# GPIO.net
KiCad netlist of a schematic drawn in Altium Designer
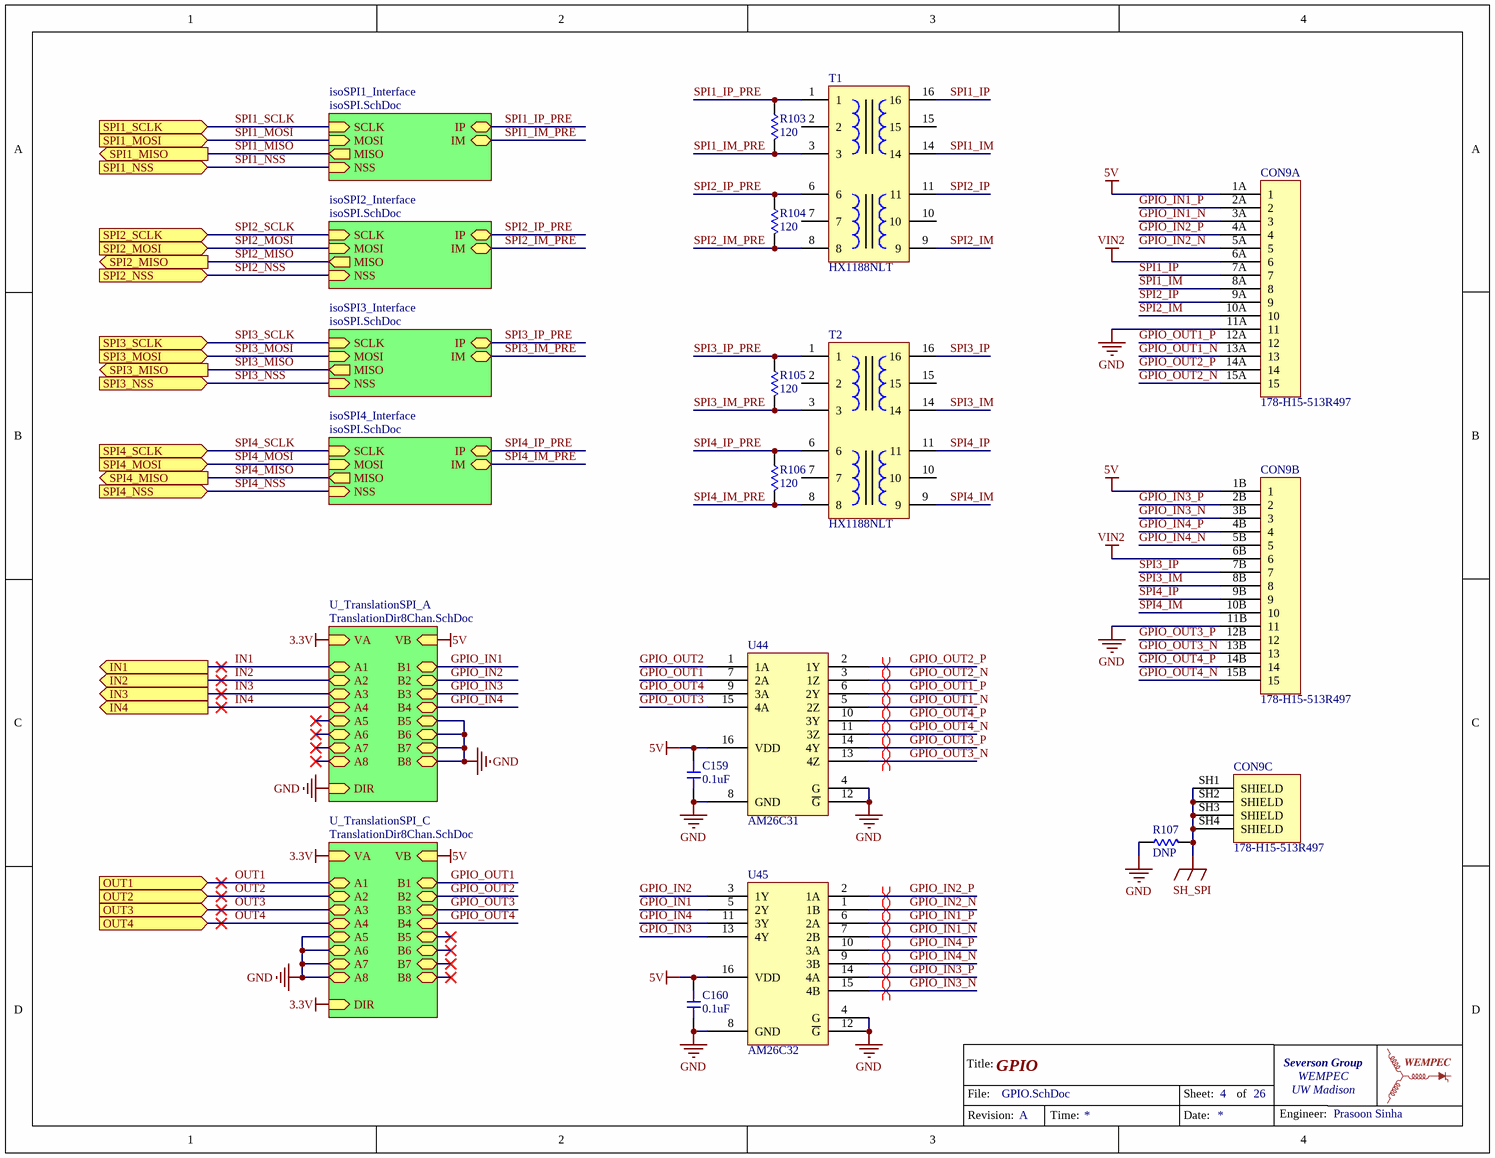
[diagram p0: GPIO.SchDoc]

(export (version "E")
  (design (tool "Eeschema 10.0.6"))
  (components
    (comp (ref "C159")
      (value "0.1uF")
      (footprint "AMDC:0603-CAP")
      (description "Capacitor")
      (libsource (lib "AMDC") (part "Capacitor"))
    )
    (comp (ref "C160")
      (value "0.1uF")
      (footprint "AMDC:0603-CAP")
      (description "Capacitor")
      (libsource (lib "AMDC") (part "Capacitor"))
    )
    (comp (ref "CON9")
      (value "178-H15-513R497")
      (footprint "AMDC:178-H15-513R497")
      (description "CONN D-SUB RCPT/RCPT 15/15POS RA")
      (libsource (lib "AMDC") (part "178-H15-513R497"))
    )
    (comp (ref "R103")
      (value "120")
      (footprint "AMDC:0603-RES")
      (description "Resistor")
      (libsource (lib "AMDC") (part "Resistor"))
    )
    (comp (ref "R104")
      (value "120")
      (footprint "AMDC:0603-RES")
      (description "Resistor")
      (libsource (lib "AMDC") (part "Resistor"))
    )
    (comp (ref "R105")
      (value "120")
      (footprint "AMDC:0603-RES")
      (description "Resistor")
      (libsource (lib "AMDC") (part "Resistor"))
    )
    (comp (ref "R106")
      (value "120")
      (footprint "AMDC:0603-RES")
      (description "Resistor")
      (libsource (lib "AMDC") (part "Resistor"))
    )
    (comp (ref "R107")
      (value "DNP")
      (footprint "AMDC:0603-RES")
      (description "Resistor")
      (libsource (lib "AMDC") (part "Resistor"))
    )
    (comp (ref "T1")
      (value "HX1188NLT")
      (footprint "AMDC:HX1188NLT")
      (description "XFRMR MAGNETIC 1PORT 1:1 10/100")
      (libsource (lib "AMDC") (part "HX1188NLT"))
    )
    (comp (ref "T2")
      (value "HX1188NLT")
      (footprint "AMDC:HX1188NLT")
      (description "XFRMR MAGNETIC 1PORT 1:1 10/100")
      (libsource (lib "AMDC") (part "HX1188NLT"))
    )
    (comp (ref "U44")
      (value "AM26C31")
      (footprint "AMDC:TSOP65P640X120-16N")
      (description "IC DRIVER 4/0 16TSSOP")
      (libsource (lib "AMDC") (part "AM26C31"))
    )
    (comp (ref "U45")
      (value "AM26C32")
      (footprint "AMDC:TSOP65P640X120-16N")
      (description "IC RCVR RS422 QUAD DIFF 16TSSOP")
      (libsource (lib "AMDC") (part "AM26C32"))
    )
  )
  (nets
    (net (code "9") (name "/GPIO_IN1") (class "Default")
      (node (ref "U45") (pin "5") (pinfunction "2Y_5") (pintype "passive"))
    )
    (net (code "10") (name "/GPIO_IN1_N") (class "Default")
      (node (ref "CON9") (pin "3A") (pinfunction "3_3A") (pintype "passive"))
      (node (ref "U45") (pin "7") (pinfunction "2B_7") (pintype "passive"))
    )
    (net (code "11") (name "/GPIO_IN1_P") (class "Default")
      (node (ref "CON9") (pin "2A") (pinfunction "2_2A") (pintype "passive"))
      (node (ref "U45") (pin "6") (pinfunction "2A_6") (pintype "passive"))
    )
    (net (code "12") (name "/GPIO_IN2") (class "Default")
      (node (ref "U45") (pin "3") (pinfunction "1Y_3") (pintype "passive"))
    )
    (net (code "13") (name "/GPIO_IN2_N") (class "Default")
      (node (ref "CON9") (pin "5A") (pinfunction "5_5A") (pintype "passive"))
      (node (ref "U45") (pin "1") (pinfunction "1B_1") (pintype "passive"))
    )
    (net (code "14") (name "/GPIO_IN2_P") (class "Default")
      (node (ref "CON9") (pin "4A") (pinfunction "4_4A") (pintype "passive"))
      (node (ref "U45") (pin "2") (pinfunction "1A_2") (pintype "passive"))
    )
    (net (code "15") (name "/GPIO_IN3") (class "Default")
      (node (ref "U45") (pin "13") (pinfunction "4Y_13") (pintype "passive"))
    )
    (net (code "16") (name "/GPIO_IN3_N") (class "Default")
      (node (ref "CON9") (pin "3B") (pinfunction "3_3B") (pintype "passive"))
      (node (ref "U45") (pin "15") (pinfunction "4B_15") (pintype "passive"))
    )
    (net (code "17") (name "/GPIO_IN3_P") (class "Default")
      (node (ref "CON9") (pin "2B") (pinfunction "2_2B") (pintype "passive"))
      (node (ref "U45") (pin "14") (pinfunction "4A_14") (pintype "passive"))
    )
    (net (code "18") (name "/GPIO_IN4") (class "Default")
      (node (ref "U45") (pin "11") (pinfunction "3Y_11") (pintype "passive"))
    )
    (net (code "19") (name "/GPIO_IN4_N") (class "Default")
      (node (ref "CON9") (pin "5B") (pinfunction "5_5B") (pintype "passive"))
      (node (ref "U45") (pin "9") (pinfunction "3B_9") (pintype "passive"))
    )
    (net (code "20") (name "/GPIO_IN4_P") (class "Default")
      (node (ref "CON9") (pin "4B") (pinfunction "4_4B") (pintype "passive"))
      (node (ref "U45") (pin "10") (pinfunction "3A_10") (pintype "passive"))
    )
    (net (code "21") (name "/GPIO_OUT1") (class "Default")
      (node (ref "U44") (pin "7") (pinfunction "2A_7") (pintype "passive"))
    )
    (net (code "22") (name "/GPIO_OUT1_N") (class "Default")
      (node (ref "CON9") (pin "13A") (pinfunction "13_13A") (pintype "passive"))
      (node (ref "U44") (pin "5") (pinfunction "2Z_5") (pintype "passive"))
    )
    (net (code "23") (name "/GPIO_OUT1_P") (class "Default")
      (node (ref "CON9") (pin "12A") (pinfunction "12_12A") (pintype "passive"))
      (node (ref "U44") (pin "6") (pinfunction "2Y_6") (pintype "passive"))
    )
    (net (code "24") (name "/GPIO_OUT2") (class "Default")
      (node (ref "U44") (pin "1") (pinfunction "1A_1") (pintype "passive"))
    )
    (net (code "25") (name "/GPIO_OUT2_N") (class "Default")
      (node (ref "CON9") (pin "15A") (pinfunction "15_15A") (pintype "passive"))
      (node (ref "U44") (pin "3") (pinfunction "1Z_3") (pintype "passive"))
    )
    (net (code "26") (name "/GPIO_OUT2_P") (class "Default")
      (node (ref "CON9") (pin "14A") (pinfunction "14_14A") (pintype "passive"))
      (node (ref "U44") (pin "2") (pinfunction "1Y_2") (pintype "passive"))
    )
    (net (code "27") (name "/GPIO_OUT3") (class "Default")
      (node (ref "U44") (pin "15") (pinfunction "4A_15") (pintype "passive"))
    )
    (net (code "28") (name "/GPIO_OUT3_N") (class "Default")
      (node (ref "CON9") (pin "13B") (pinfunction "13_13B") (pintype "passive"))
      (node (ref "U44") (pin "13") (pinfunction "4Z_13") (pintype "passive"))
    )
    (net (code "29") (name "/GPIO_OUT3_P") (class "Default")
      (node (ref "CON9") (pin "12B") (pinfunction "12_12B") (pintype "passive"))
      (node (ref "U44") (pin "14") (pinfunction "4Y_14") (pintype "passive"))
    )
    (net (code "30") (name "/GPIO_OUT4") (class "Default")
      (node (ref "U44") (pin "9") (pinfunction "3A_9") (pintype "passive"))
    )
    (net (code "31") (name "/GPIO_OUT4_N") (class "Default")
      (node (ref "CON9") (pin "15B") (pinfunction "15_15B") (pintype "passive"))
      (node (ref "U44") (pin "11") (pinfunction "3Z_11") (pintype "passive"))
    )
    (net (code "32") (name "/GPIO_OUT4_P") (class "Default")
      (node (ref "CON9") (pin "14B") (pinfunction "14_14B") (pintype "passive"))
      (node (ref "U44") (pin "10") (pinfunction "3Y_10") (pintype "passive"))
    )
    (net (code "41") (name "/SPI1_IM") (class "Default")
      (node (ref "CON9") (pin "8A") (pinfunction "8_8A") (pintype "passive"))
      (node (ref "T1") (pin "14") (pinfunction "14_14") (pintype "passive"))
    )
    (net (code "42") (name "/SPI1_IM_PRE") (class "Default")
      (node (ref "R103") (pin "2") (pinfunction "2_2") (pintype "passive"))
      (node (ref "T1") (pin "3") (pinfunction "3_3") (pintype "passive"))
    )
    (net (code "43") (name "/SPI1_IP") (class "Default")
      (node (ref "CON9") (pin "7A") (pinfunction "7_7A") (pintype "passive"))
      (node (ref "T1") (pin "16") (pinfunction "16_16") (pintype "passive"))
    )
    (net (code "44") (name "/SPI1_IP_PRE") (class "Default")
      (node (ref "R103") (pin "1") (pinfunction "1_1") (pintype "passive"))
      (node (ref "T1") (pin "1") (pinfunction "1_1") (pintype "passive"))
    )
    (net (code "49") (name "/SPI2_IM") (class "Default")
      (node (ref "CON9") (pin "10A") (pinfunction "10_10A") (pintype "passive"))
      (node (ref "T1") (pin "9") (pinfunction "9_9") (pintype "passive"))
    )
    (net (code "50") (name "/SPI2_IM_PRE") (class "Default")
      (node (ref "R104") (pin "2") (pinfunction "2_2") (pintype "passive"))
      (node (ref "T1") (pin "8") (pinfunction "8_8") (pintype "passive"))
    )
    (net (code "51") (name "/SPI2_IP") (class "Default")
      (node (ref "CON9") (pin "9A") (pinfunction "9_9A") (pintype "passive"))
      (node (ref "T1") (pin "11") (pinfunction "11_11") (pintype "passive"))
    )
    (net (code "52") (name "/SPI2_IP_PRE") (class "Default")
      (node (ref "R104") (pin "1") (pinfunction "1_1") (pintype "passive"))
      (node (ref "T1") (pin "6") (pinfunction "6_6") (pintype "passive"))
    )
    (net (code "57") (name "/SPI3_IM") (class "Default")
      (node (ref "CON9") (pin "8B") (pinfunction "8_8B") (pintype "passive"))
      (node (ref "T2") (pin "14") (pinfunction "14_14") (pintype "passive"))
    )
    (net (code "58") (name "/SPI3_IM_PRE") (class "Default")
      (node (ref "R105") (pin "2") (pinfunction "2_2") (pintype "passive"))
      (node (ref "T2") (pin "3") (pinfunction "3_3") (pintype "passive"))
    )
    (net (code "59") (name "/SPI3_IP") (class "Default")
      (node (ref "CON9") (pin "7B") (pinfunction "7_7B") (pintype "passive"))
      (node (ref "T2") (pin "16") (pinfunction "16_16") (pintype "passive"))
    )
    (net (code "60") (name "/SPI3_IP_PRE") (class "Default")
      (node (ref "R105") (pin "1") (pinfunction "1_1") (pintype "passive"))
      (node (ref "T2") (pin "1") (pinfunction "1_1") (pintype "passive"))
    )
    (net (code "65") (name "/SPI4_IM") (class "Default")
      (node (ref "CON9") (pin "10B") (pinfunction "10_10B") (pintype "passive"))
      (node (ref "T2") (pin "9") (pinfunction "9_9") (pintype "passive"))
    )
    (net (code "66") (name "/SPI4_IM_PRE") (class "Default")
      (node (ref "R106") (pin "2") (pinfunction "2_2") (pintype "passive"))
      (node (ref "T2") (pin "8") (pinfunction "8_8") (pintype "passive"))
    )
    (net (code "67") (name "/SPI4_IP") (class "Default")
      (node (ref "CON9") (pin "9B") (pinfunction "9_9B") (pintype "passive"))
      (node (ref "T2") (pin "11") (pinfunction "11_11") (pintype "passive"))
    )
    (net (code "68") (name "/SPI4_IP_PRE") (class "Default")
      (node (ref "R106") (pin "1") (pinfunction "1_1") (pintype "passive"))
      (node (ref "T2") (pin "6") (pinfunction "6_6") (pintype "passive"))
    )
    (net (code "74") (name "5V") (class "Default")
      (node (ref "C159") (pin "1") (pinfunction "1_1") (pintype "passive"))
      (node (ref "C160") (pin "1") (pinfunction "1_1") (pintype "passive"))
      (node (ref "CON9") (pin "1A") (pinfunction "1_1A") (pintype "passive"))
      (node (ref "CON9") (pin "1B") (pinfunction "1_1B") (pintype "passive"))
      (node (ref "U44") (pin "16") (pinfunction "VDD_16") (pintype "passive"))
      (node (ref "U45") (pin "16") (pinfunction "VDD_16") (pintype "passive"))
    )
    (net (code "75") (name "GND") (class "Default")
      (node (ref "C159") (pin "2") (pinfunction "2_2") (pintype "passive"))
      (node (ref "C160") (pin "2") (pinfunction "2_2") (pintype "passive"))
      (node (ref "CON9") (pin "11A") (pinfunction "11_11A") (pintype "passive"))
      (node (ref "CON9") (pin "11B") (pinfunction "11_11B") (pintype "passive"))
      (node (ref "R107") (pin "1") (pinfunction "1_1") (pintype "passive"))
      (node (ref "U44") (pin "12") (pinfunction "~{G}_12") (pintype "passive"))
      (node (ref "U44") (pin "4") (pinfunction "G_4") (pintype "passive"))
      (node (ref "U44") (pin "8") (pinfunction "GND_8") (pintype "passive"))
      (node (ref "U45") (pin "12") (pinfunction "~{G}_12") (pintype "passive"))
      (node (ref "U45") (pin "4") (pinfunction "G_4") (pintype "passive"))
      (node (ref "U45") (pin "8") (pinfunction "GND_8") (pintype "passive"))
    )
    (net (code "76") (name "SH_SPI") (class "Default")
      (node (ref "CON9") (pin "SH1") (pinfunction "SHIELD_SH1") (pintype "passive"))
      (node (ref "CON9") (pin "SH2") (pinfunction "SHIELD_SH2") (pintype "passive"))
      (node (ref "CON9") (pin "SH3") (pinfunction "SHIELD_SH3") (pintype "passive"))
      (node (ref "CON9") (pin "SH4") (pinfunction "SHIELD_SH4") (pintype "passive"))
      (node (ref "R107") (pin "2") (pinfunction "2_2") (pintype "passive"))
    )
    (net (code "77") (name "VIN2") (class "Default")
      (node (ref "CON9") (pin "6A") (pinfunction "6_6A") (pintype "passive"))
      (node (ref "CON9") (pin "6B") (pinfunction "6_6B") (pintype "passive"))
    )
    (net (code "78") (name "unconnected-(T1-Pad2)") (class "Default")
      (node (ref "T1") (pin "2") (pinfunction "2_2") (pintype "passive"))
    )
    (net (code "79") (name "unconnected-(T1-Pad7)") (class "Default")
      (node (ref "T1") (pin "7") (pinfunction "7_7") (pintype "passive"))
    )
    (net (code "80") (name "unconnected-(T1-Pad10)") (class "Default")
      (node (ref "T1") (pin "10") (pinfunction "10_10") (pintype "passive"))
    )
    (net (code "81") (name "unconnected-(T1-Pad15)") (class "Default")
      (node (ref "T1") (pin "15") (pinfunction "15_15") (pintype "passive"))
    )
    (net (code "82") (name "unconnected-(T2-Pad2)") (class "Default")
      (node (ref "T2") (pin "2") (pinfunction "2_2") (pintype "passive"))
    )
    (net (code "83") (name "unconnected-(T2-Pad7)") (class "Default")
      (node (ref "T2") (pin "7") (pinfunction "7_7") (pintype "passive"))
    )
    (net (code "84") (name "unconnected-(T2-Pad10)") (class "Default")
      (node (ref "T2") (pin "10") (pinfunction "10_10") (pintype "passive"))
    )
    (net (code "85") (name "unconnected-(T2-Pad15)") (class "Default")
      (node (ref "T2") (pin "15") (pinfunction "15_15") (pintype "passive"))
    )
  )
)
